# ir_blaster.net
KiCad netlist of a schematic drawn in EAGLE
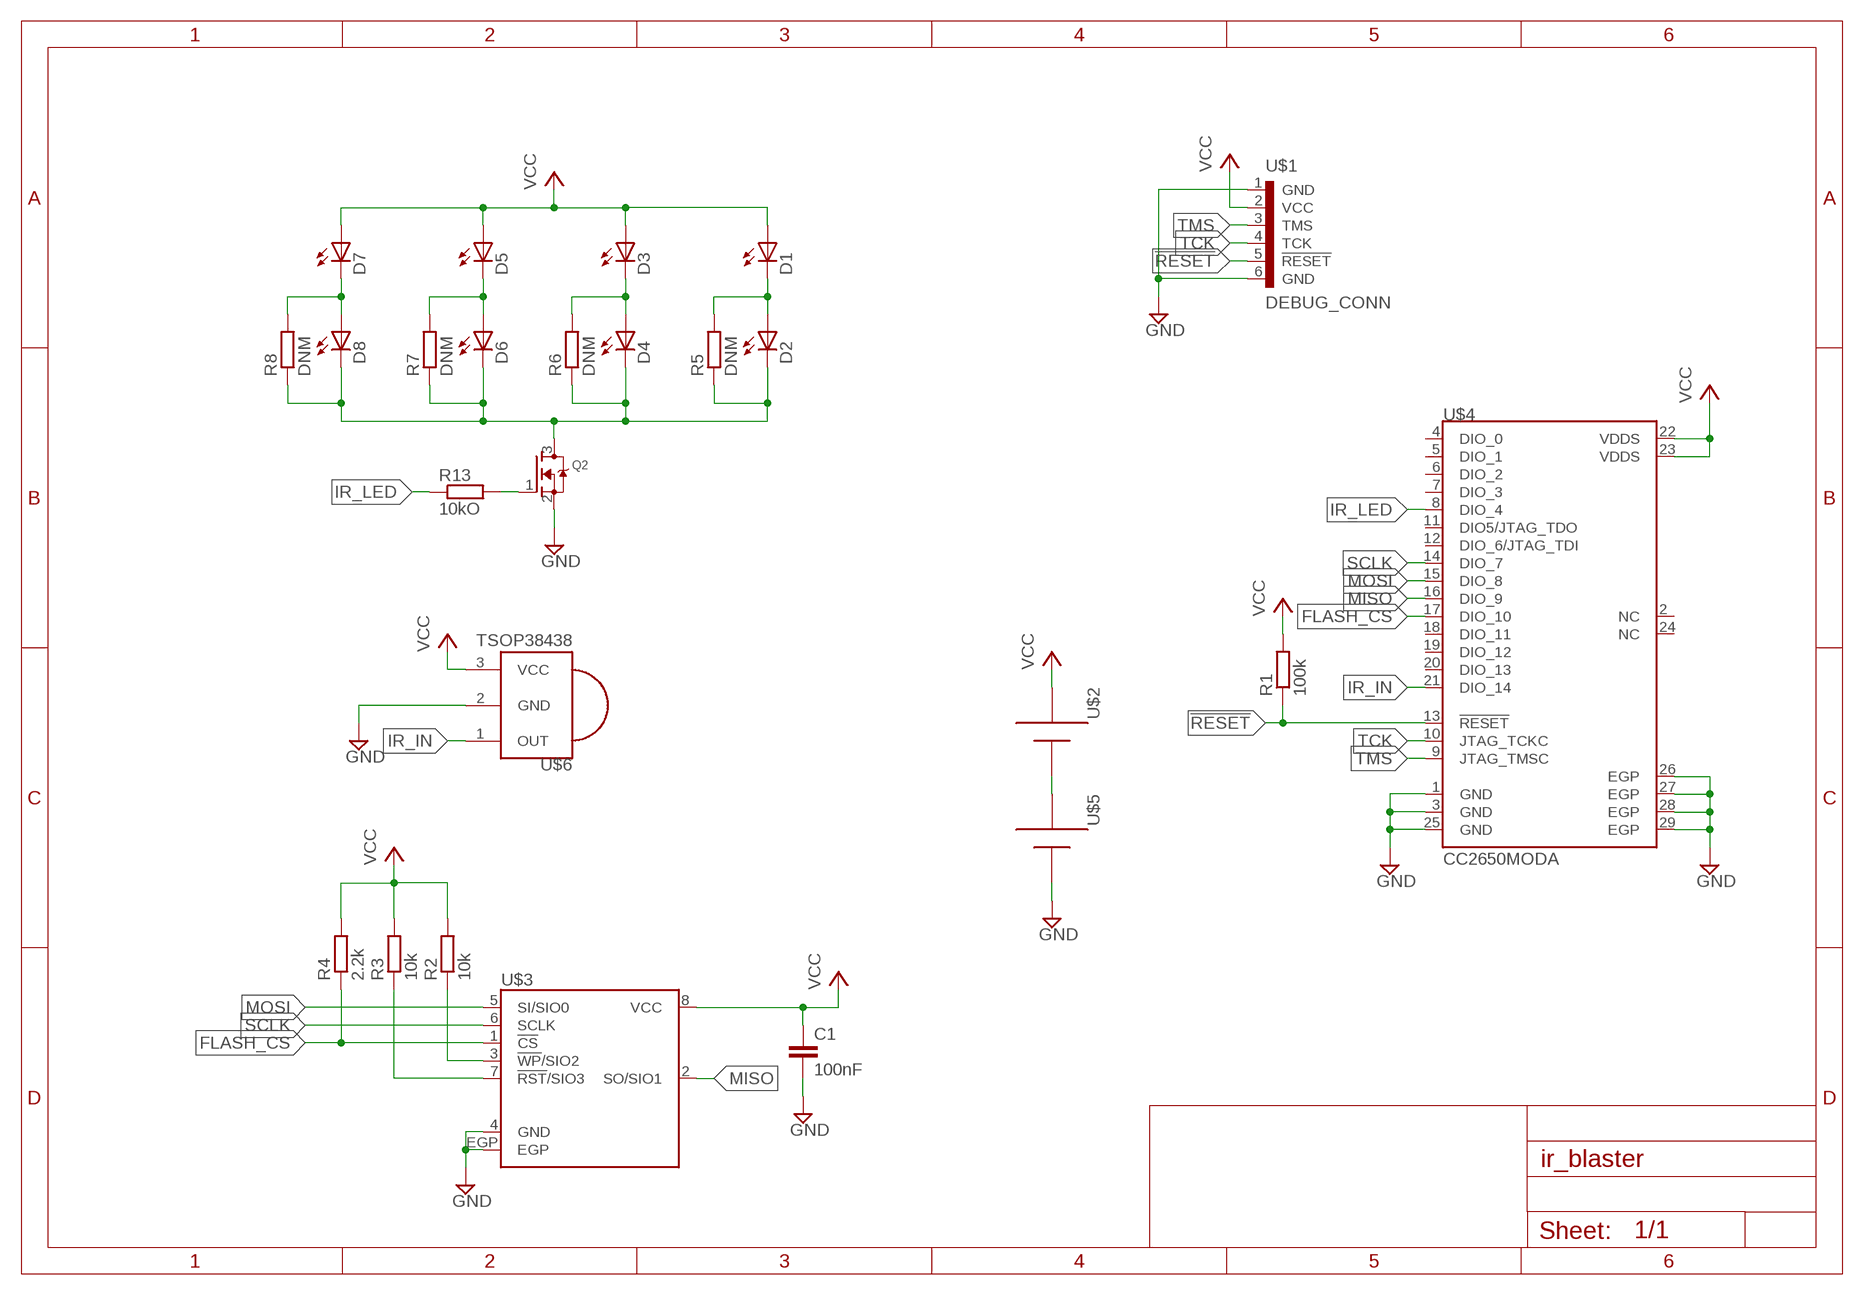
[diagram p0: schematic, sheet 1]

(export (version "E")
  (design (tool "Eeschema 10.0.6"))
  (components
    (comp (ref "C1")
      (value "100nF")
      (footprint "eagle-import:0402")
      (libsource (lib "eagle-import") (part "CAPACITOR_0402"))
    )
    (comp (ref "D1")
      (value "SFH482")
      (footprint "eagle-import:SFH482")
      (libsource (lib "eagle-import") (part "SFH482"))
    )
    (comp (ref "D2")
      (value "SFH482")
      (footprint "eagle-import:SFH482")
      (libsource (lib "eagle-import") (part "SFH482"))
    )
    (comp (ref "D3")
      (value "SFH482")
      (footprint "eagle-import:SFH482")
      (libsource (lib "eagle-import") (part "SFH482"))
    )
    (comp (ref "D4")
      (value "SFH482")
      (footprint "eagle-import:SFH482")
      (libsource (lib "eagle-import") (part "SFH482"))
    )
    (comp (ref "D5")
      (value "SFH482")
      (footprint "eagle-import:SFH482")
      (libsource (lib "eagle-import") (part "SFH482"))
    )
    (comp (ref "D6")
      (value "SFH482")
      (footprint "eagle-import:SFH482")
      (libsource (lib "eagle-import") (part "SFH482"))
    )
    (comp (ref "D7")
      (value "SFH482")
      (footprint "eagle-import:SFH482")
      (libsource (lib "eagle-import") (part "SFH482"))
    )
    (comp (ref "D8")
      (value "SFH482")
      (footprint "eagle-import:SFH482")
      (libsource (lib "eagle-import") (part "SFH482"))
    )
    (comp (ref "Q2")
      (value "MOSFET-NREFLOW")
      (footprint "eagle-import:SOT23")
      (libsource (lib "eagle-import") (part "MOSFET-NREFLOW"))
    )
    (comp (ref "R1")
      (value "100k")
      (footprint "eagle-import:0402")
      (libsource (lib "eagle-import") (part "RESISTOR_0402"))
    )
    (comp (ref "R2")
      (value "10k")
      (footprint "eagle-import:0402")
      (libsource (lib "eagle-import") (part "RESISTOR_0402"))
    )
    (comp (ref "R3")
      (value "10k")
      (footprint "eagle-import:0402")
      (libsource (lib "eagle-import") (part "RESISTOR_0402"))
    )
    (comp (ref "R4")
      (value "2.2k")
      (footprint "eagle-import:0402")
      (libsource (lib "eagle-import") (part "RESISTOR_0402"))
    )
    (comp (ref "R5")
      (value "DNM")
      (footprint "eagle-import:0402")
      (libsource (lib "eagle-import") (part "RESISTOR_0402"))
    )
    (comp (ref "R6")
      (value "DNM")
      (footprint "eagle-import:0402")
      (libsource (lib "eagle-import") (part "RESISTOR_0402"))
    )
    (comp (ref "R7")
      (value "DNM")
      (footprint "eagle-import:0402")
      (libsource (lib "eagle-import") (part "RESISTOR_0402"))
    )
    (comp (ref "R8")
      (value "DNM")
      (footprint "eagle-import:0402")
      (libsource (lib "eagle-import") (part "RESISTOR_0402"))
    )
    (comp (ref "R13")
      (value "10kO")
      (footprint "eagle-import:0402")
      (libsource (lib "eagle-import") (part "RESISTOR_0402"))
    )
    (comp (ref "U$1")
      (value "DEBUG_CONN")
      (footprint "eagle-import:DEBUG_CONN")
      (libsource (lib "eagle-import") (part "DEBUG_CONN"))
    )
    (comp (ref "U$2") (value "AA") (footprint "eagle-import:AA") (libsource (lib "eagle-import") (part "AA")))
    (comp (ref "U$3")
      (value "MX25R8035FMX25R8035FZUIL0")
      (footprint "eagle-import:MX25R8035FZUIL0")
      (libsource (lib "eagle-import") (part "MX25R8035FMX25R8035FZUIL0"))
    )
    (comp (ref "U$4")
      (value "CC2650MODA")
      (footprint "eagle-import:CC2650MODA")
      (libsource (lib "eagle-import") (part "CC2650MODA"))
    )
    (comp (ref "U$5") (value "AA") (footprint "eagle-import:AA") (libsource (lib "eagle-import") (part "AA")))
    (comp (ref "U$6")
      (value "TSOP38438")
      (footprint "eagle-import:PNA460XM")
      (libsource (lib "eagle-import") (part "PNA460XM"))
    )
  )
  (nets
    (net (code "1") (name "/~{RESET}") (class "Default")
      (node (ref "R1") (pin "1") (pinfunction "1_1") (pintype "passive"))
      (node (ref "U$1") (pin "5") (pinfunction "~{RESET}_5") (pintype "bidirectional"))
      (node (ref "U$4") (pin "13") (pinfunction "~{RESET}_13") (pintype "bidirectional"))
    )
    (net (code "2") (name "FLASH_CS") (class "Default")
      (node (ref "R4") (pin "1") (pinfunction "1_1") (pintype "passive"))
      (node (ref "U$3") (pin "1") (pinfunction "~{CS}_1") (pintype "input"))
      (node (ref "U$4") (pin "17") (pinfunction "DIO_10_17") (pintype "bidirectional"))
    )
    (net (code "3") (name "GND") (class "Default")
      (node (ref "C1") (pin "2") (pinfunction "2_2") (pintype "passive"))
      (node (ref "Q2") (pin "2") (pinfunction "S_2") (pintype "bidirectional"))
      (node (ref "U$1") (pin "1") (pinfunction "GND_1") (pintype "bidirectional"))
      (node (ref "U$1") (pin "6") (pinfunction "GND_6") (pintype "bidirectional"))
      (node (ref "U$3") (pin "4") (pinfunction "GND_4") (pintype "power_in"))
      (node (ref "U$3") (pin "EGP") (pinfunction "EGP_EGP") (pintype "power_in"))
      (node (ref "U$4") (pin "1") (pinfunction "GND_1") (pintype "power_in"))
      (node (ref "U$4") (pin "25") (pinfunction "GND_25") (pintype "power_in"))
      (node (ref "U$4") (pin "26") (pinfunction "EGP_26") (pintype "power_in"))
      (node (ref "U$4") (pin "27") (pinfunction "EGP_27") (pintype "power_in"))
      (node (ref "U$4") (pin "28") (pinfunction "EGP_28") (pintype "power_in"))
      (node (ref "U$4") (pin "29") (pinfunction "EGP_29") (pintype "power_in"))
      (node (ref "U$4") (pin "3") (pinfunction "GND_3") (pintype "power_in"))
      (node (ref "U$5") (pin "-") (pinfunction "-_-") (pintype "bidirectional"))
      (node (ref "U$5") (pin "-@1") (pinfunction "-_-@1") (pintype "bidirectional"))
      (node (ref "U$5") (pin "-@2") (pinfunction "-_-@2") (pintype "bidirectional"))
      (node (ref "U$5") (pin "-@3") (pinfunction "-_-@3") (pintype "bidirectional"))
      (node (ref "U$6") (pin "2") (pinfunction "GND_2") (pintype "power_in"))
    )
    (net (code "4") (name "IR_IN") (class "Default")
      (node (ref "U$4") (pin "21") (pinfunction "DIO_14_21") (pintype "bidirectional"))
      (node (ref "U$6") (pin "1") (pinfunction "OUT_1") (pintype "output"))
    )
    (net (code "5") (name "IR_LED") (class "Default")
      (node (ref "R13") (pin "1") (pinfunction "1_1") (pintype "passive"))
      (node (ref "U$4") (pin "8") (pinfunction "DIO_4_8") (pintype "bidirectional"))
    )
    (net (code "6") (name "MISO") (class "Default")
      (node (ref "U$3") (pin "2") (pinfunction "SO/SIO1_2") (pintype "bidirectional"))
      (node (ref "U$4") (pin "16") (pinfunction "DIO_9_16") (pintype "bidirectional"))
    )
    (net (code "7") (name "MOSI") (class "Default")
      (node (ref "U$3") (pin "5") (pinfunction "SI/SIO0_5") (pintype "bidirectional"))
      (node (ref "U$4") (pin "15") (pinfunction "DIO_8_15") (pintype "bidirectional"))
    )
    (net (code "8") (name "Net-(D1-C)") (class "Default")
      (node (ref "D1") (pin "K") (pinfunction "C_K") (pintype "passive"))
      (node (ref "D2") (pin "A") (pinfunction "A_A") (pintype "passive"))
      (node (ref "R5") (pin "2") (pinfunction "2_2") (pintype "passive"))
    )
    (net (code "9") (name "Net-(D2-C)") (class "Default")
      (node (ref "D2") (pin "K") (pinfunction "C_K") (pintype "passive"))
      (node (ref "D4") (pin "K") (pinfunction "C_K") (pintype "passive"))
      (node (ref "D6") (pin "K") (pinfunction "C_K") (pintype "passive"))
      (node (ref "D8") (pin "K") (pinfunction "C_K") (pintype "passive"))
      (node (ref "Q2") (pin "3") (pinfunction "D_3") (pintype "bidirectional"))
      (node (ref "R5") (pin "1") (pinfunction "1_1") (pintype "passive"))
      (node (ref "R6") (pin "1") (pinfunction "1_1") (pintype "passive"))
      (node (ref "R7") (pin "1") (pinfunction "1_1") (pintype "passive"))
      (node (ref "R8") (pin "1") (pinfunction "1_1") (pintype "passive"))
    )
    (net (code "10") (name "Net-(D3-C)") (class "Default")
      (node (ref "D3") (pin "K") (pinfunction "C_K") (pintype "passive"))
      (node (ref "D4") (pin "A") (pinfunction "A_A") (pintype "passive"))
      (node (ref "R6") (pin "2") (pinfunction "2_2") (pintype "passive"))
    )
    (net (code "11") (name "Net-(D5-C)") (class "Default")
      (node (ref "D5") (pin "K") (pinfunction "C_K") (pintype "passive"))
      (node (ref "D6") (pin "A") (pinfunction "A_A") (pintype "passive"))
      (node (ref "R7") (pin "2") (pinfunction "2_2") (pintype "passive"))
    )
    (net (code "12") (name "Net-(D7-C)") (class "Default")
      (node (ref "D7") (pin "K") (pinfunction "C_K") (pintype "passive"))
      (node (ref "D8") (pin "A") (pinfunction "A_A") (pintype "passive"))
      (node (ref "R8") (pin "2") (pinfunction "2_2") (pintype "passive"))
    )
    (net (code "13") (name "Net-(Q2-G)") (class "Default")
      (node (ref "Q2") (pin "1") (pinfunction "G_1") (pintype "bidirectional"))
      (node (ref "R13") (pin "2") (pinfunction "2_2") (pintype "passive"))
    )
    (net (code "14") (name "Net-(U$2---Pad-@1)") (class "Default")
      (node (ref "U$2") (pin "-") (pinfunction "-_-") (pintype "bidirectional"))
      (node (ref "U$2") (pin "-@1") (pinfunction "-_-@1") (pintype "bidirectional"))
      (node (ref "U$2") (pin "-@2") (pinfunction "-_-@2") (pintype "bidirectional"))
      (node (ref "U$2") (pin "-@3") (pinfunction "-_-@3") (pintype "bidirectional"))
      (node (ref "U$5") (pin "+") (pinfunction "+_+") (pintype "bidirectional"))
      (node (ref "U$5") (pin "+@1") (pinfunction "+_+@1") (pintype "bidirectional"))
      (node (ref "U$5") (pin "+@2") (pinfunction "+_+@2") (pintype "bidirectional"))
      (node (ref "U$5") (pin "+@3") (pinfunction "+_+@3") (pintype "bidirectional"))
    )
    (net (code "15") (name "Net-(U$3-~{RST}{slash}SIO3)") (class "Default")
      (node (ref "R3") (pin "1") (pinfunction "1_1") (pintype "passive"))
      (node (ref "U$3") (pin "7") (pinfunction "~{RST}/SIO3_7") (pintype "bidirectional"))
    )
    (net (code "16") (name "Net-(U$3-~{WP}{slash}SIO2)") (class "Default")
      (node (ref "R2") (pin "1") (pinfunction "1_1") (pintype "passive"))
      (node (ref "U$3") (pin "3") (pinfunction "~{WP}/SIO2_3") (pintype "bidirectional"))
    )
    (net (code "17") (name "SCLK") (class "Default")
      (node (ref "U$3") (pin "6") (pinfunction "SCLK_6") (pintype "input"))
      (node (ref "U$4") (pin "14") (pinfunction "DIO_7_14") (pintype "bidirectional"))
    )
    (net (code "18") (name "TCK") (class "Default")
      (node (ref "U$1") (pin "4") (pinfunction "TCK_4") (pintype "bidirectional"))
      (node (ref "U$4") (pin "10") (pinfunction "JTAG_TCKC_10") (pintype "bidirectional"))
    )
    (net (code "19") (name "TMS") (class "Default")
      (node (ref "U$1") (pin "3") (pinfunction "TMS_3") (pintype "bidirectional"))
      (node (ref "U$4") (pin "9") (pinfunction "JTAG_TMSC_9") (pintype "bidirectional"))
    )
    (net (code "20") (name "VCC") (class "Default")
      (node (ref "C1") (pin "1") (pinfunction "1_1") (pintype "passive"))
      (node (ref "D1") (pin "A") (pinfunction "A_A") (pintype "passive"))
      (node (ref "D3") (pin "A") (pinfunction "A_A") (pintype "passive"))
      (node (ref "D5") (pin "A") (pinfunction "A_A") (pintype "passive"))
      (node (ref "D7") (pin "A") (pinfunction "A_A") (pintype "passive"))
      (node (ref "R1") (pin "2") (pinfunction "2_2") (pintype "passive"))
      (node (ref "R2") (pin "2") (pinfunction "2_2") (pintype "passive"))
      (node (ref "R3") (pin "2") (pinfunction "2_2") (pintype "passive"))
      (node (ref "R4") (pin "2") (pinfunction "2_2") (pintype "passive"))
      (node (ref "U$1") (pin "2") (pinfunction "VCC_2") (pintype "bidirectional"))
      (node (ref "U$2") (pin "+") (pinfunction "+_+") (pintype "bidirectional"))
      (node (ref "U$2") (pin "+@1") (pinfunction "+_+@1") (pintype "bidirectional"))
      (node (ref "U$2") (pin "+@2") (pinfunction "+_+@2") (pintype "bidirectional"))
      (node (ref "U$2") (pin "+@3") (pinfunction "+_+@3") (pintype "bidirectional"))
      (node (ref "U$3") (pin "8") (pinfunction "VCC_8") (pintype "power_in"))
      (node (ref "U$4") (pin "22") (pinfunction "VDDS_22") (pintype "power_in"))
      (node (ref "U$4") (pin "23") (pinfunction "VDDS_23") (pintype "power_in"))
      (node (ref "U$6") (pin "3") (pinfunction "VCC_3") (pintype "power_in"))
    )
    (net (code "21") (name "unconnected-(U$4-DIO5{slash}JTAG_TDO-Pad11)") (class "Default")
      (node (ref "U$4") (pin "11") (pinfunction "DIO5/JTAG_TDO_11") (pintype "bidirectional"))
    )
    (net (code "22") (name "unconnected-(U$4-DIO_0-Pad4)") (class "Default")
      (node (ref "U$4") (pin "4") (pinfunction "DIO_0_4") (pintype "bidirectional"))
    )
    (net (code "23") (name "unconnected-(U$4-DIO_1-Pad5)") (class "Default")
      (node (ref "U$4") (pin "5") (pinfunction "DIO_1_5") (pintype "bidirectional"))
    )
    (net (code "24") (name "unconnected-(U$4-DIO_2-Pad6)") (class "Default")
      (node (ref "U$4") (pin "6") (pinfunction "DIO_2_6") (pintype "bidirectional"))
    )
    (net (code "25") (name "unconnected-(U$4-DIO_3-Pad7)") (class "Default")
      (node (ref "U$4") (pin "7") (pinfunction "DIO_3_7") (pintype "bidirectional"))
    )
    (net (code "26") (name "unconnected-(U$4-DIO_6{slash}JTAG_TDI-Pad12)") (class "Default")
      (node (ref "U$4") (pin "12") (pinfunction "DIO_6/JTAG_TDI_12") (pintype "bidirectional"))
    )
    (net (code "27") (name "unconnected-(U$4-DIO_11-Pad18)") (class "Default")
      (node (ref "U$4") (pin "18") (pinfunction "DIO_11_18") (pintype "bidirectional"))
    )
    (net (code "28") (name "unconnected-(U$4-DIO_12-Pad19)") (class "Default")
      (node (ref "U$4") (pin "19") (pinfunction "DIO_12_19") (pintype "bidirectional"))
    )
    (net (code "29") (name "unconnected-(U$4-DIO_13-Pad20)") (class "Default")
      (node (ref "U$4") (pin "20") (pinfunction "DIO_13_20") (pintype "bidirectional"))
    )
    (net (code "30") (name "unconnected-(U$4-NC-Pad2)") (class "Default")
      (node (ref "U$4") (pin "2") (pinfunction "NC_2") (pintype "no_connect"))
    )
    (net (code "31") (name "unconnected-(U$4-NC-Pad24)") (class "Default")
      (node (ref "U$4") (pin "24") (pinfunction "NC_24") (pintype "no_connect"))
    )
  )
)
